# ADC.net
KiCad netlist of a schematic drawn in Altium Designer
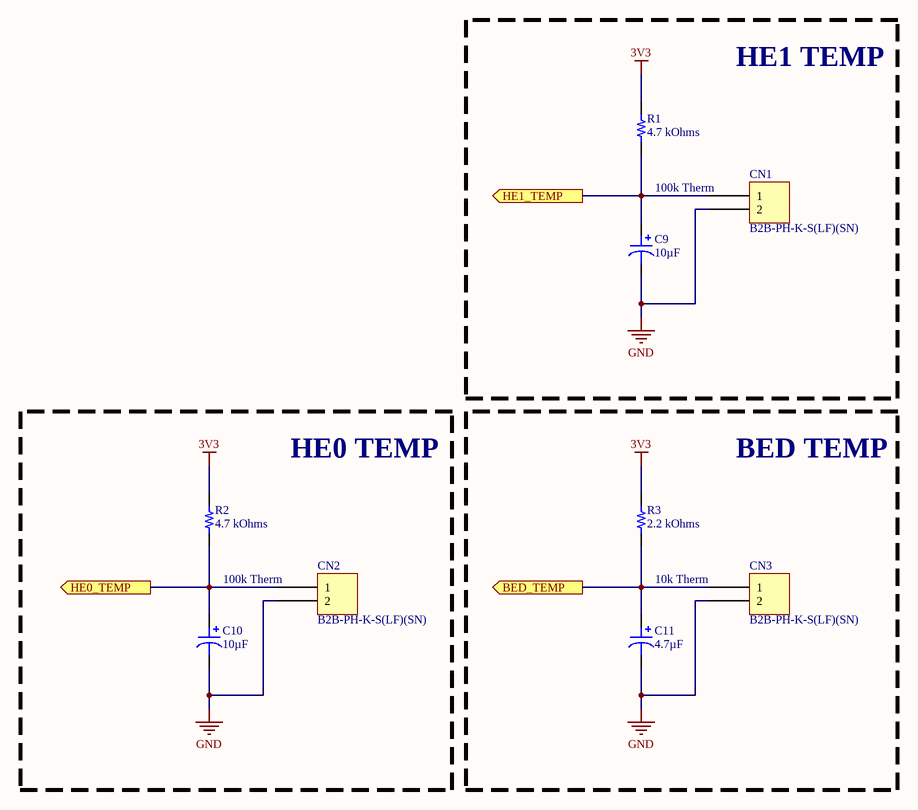
[diagram p0: ADC.SchDoc]

(export (version "E")
  (design (tool "Eeschema 10.0.6"))
  (components
    (comp (ref "C9")
      (value "10µF")
      (footprint "CAP ALSMD 5.3MM H5.4MM")
      (description "CAP ALUM 10UF 20% 16V SMD")
      (fields (field (name "PART NUMBER") "UZP1C100MCL1GB") (field (name "MANUFACTURER") "Nichicon"))
      (libsource (lib "Celestial Altium Library - altium_library") (part "Polarised Capacitor"))
    )
    (comp (ref "C10")
      (value "10µF")
      (footprint "CAP ALSMD 5.3MM H5.4MM")
      (description "CAP ALUM 10UF 20% 16V SMD")
      (fields (field (name "PART NUMBER") "UZP1C100MCL1GB") (field (name "MANUFACTURER") "Nichicon"))
      (libsource (lib "Celestial Altium Library - altium_library") (part "Polarised Capacitor"))
    )
    (comp (ref "C11")
      (value "4.7µF")
      (footprint "CAP ALSMD POLY 4.3MM H5.5MM")
      (description "CAP ALUM POLY 4.7UF 20% 10V SMD")
      (fields (field (name "PART NUMBER") "PCF1A4R7MCL1GB") (field (name "MANUFACTURER") "Nichicon"))
      (libsource (lib "Celestial Altium Library - altium_library") (part "Polarised Capacitor"))
    )
    (comp (ref "CN1")
      (value "B2B-PH-K-S(LF)(SN)")
      (footprint "JST B2B-PH-K")
      (description "CONN HEADER VERT 2POS 2MM")
      (fields (field (name "MANUFACTURER") "JST Sales America Inc."))
      (libsource (lib "Celestial Altium Library - altium_library") (part "2 Pin"))
    )
    (comp (ref "CN2")
      (value "B2B-PH-K-S(LF)(SN)")
      (footprint "JST B2B-PH-K")
      (description "CONN HEADER VERT 2POS 2MM")
      (fields (field (name "MANUFACTURER") "JST Sales America Inc."))
      (libsource (lib "Celestial Altium Library - altium_library") (part "2 Pin"))
    )
    (comp (ref "CN3")
      (value "B2B-PH-K-S(LF)(SN)")
      (footprint "JST B2B-PH-K")
      (description "CONN HEADER VERT 2POS 2MM")
      (fields (field (name "MANUFACTURER") "JST Sales America Inc."))
      (libsource (lib "Celestial Altium Library - altium_library") (part "2 Pin"))
    )
    (comp (ref "R1")
      (value "4.7 kOhms")
      (footprint "RES 0603_1608")
      (description "RES 4.7K OHM 0.1% 1/5W 0603")
      (fields
        (field (name "PART NUMBER") "RS73G1JTTD4701B")
        (field (name "MANUFACTURER") "KOA Speer Electronics, Inc.")
      )
      (libsource (lib "Celestial Altium Library - altium_library") (part "Resistor"))
    )
    (comp (ref "R2")
      (value "4.7 kOhms")
      (footprint "RES 0603_1608")
      (description "RES 4.7K OHM 0.1% 1/5W 0603")
      (fields
        (field (name "PART NUMBER") "RS73G1JTTD4701B")
        (field (name "MANUFACTURER") "KOA Speer Electronics, Inc.")
      )
      (libsource (lib "Celestial Altium Library - altium_library") (part "Resistor"))
    )
    (comp (ref "R3")
      (value "2.2 kOhms")
      (footprint "RES 0603_1608")
      (description "RES 2.2K OHM 0.1% 1/5W 0603")
      (fields
        (field (name "PART NUMBER") "RS73G1JTTD2201B")
        (field (name "MANUFACTURER") "KOA Speer Electronics, Inc.")
      )
      (libsource (lib "Celestial Altium Library - altium_library") (part "Resistor"))
    )
  )
  (nets
    (net (code "1") (name "/BED_TEMP") (class "Default")
      (node (ref "C11") (pin "1") (pinfunction "1_1") (pintype "passive"))
      (node (ref "CN3") (pin "1") (pinfunction "1_1") (pintype "passive"))
      (node (ref "R3") (pin "1") (pinfunction "1_1") (pintype "passive"))
    )
    (net (code "2") (name "/HE0_TEMP") (class "Default")
      (node (ref "C10") (pin "1") (pinfunction "1_1") (pintype "passive"))
      (node (ref "CN2") (pin "1") (pinfunction "1_1") (pintype "passive"))
      (node (ref "R2") (pin "1") (pinfunction "1_1") (pintype "passive"))
    )
    (net (code "3") (name "/HE1_TEMP") (class "Default")
      (node (ref "C9") (pin "1") (pinfunction "1_1") (pintype "passive"))
      (node (ref "CN1") (pin "1") (pinfunction "1_1") (pintype "passive"))
      (node (ref "R1") (pin "1") (pinfunction "1_1") (pintype "passive"))
    )
    (net (code "4") (name "3V3") (class "Default")
      (node (ref "R1") (pin "2") (pinfunction "2_2") (pintype "passive"))
      (node (ref "R2") (pin "2") (pinfunction "2_2") (pintype "passive"))
      (node (ref "R3") (pin "2") (pinfunction "2_2") (pintype "passive"))
    )
    (net (code "5") (name "GND") (class "Default")
      (node (ref "C10") (pin "2") (pinfunction "2_2") (pintype "passive"))
      (node (ref "C11") (pin "2") (pinfunction "2_2") (pintype "passive"))
      (node (ref "C9") (pin "2") (pinfunction "2_2") (pintype "passive"))
      (node (ref "CN1") (pin "2") (pinfunction "2_2") (pintype "passive"))
      (node (ref "CN2") (pin "2") (pinfunction "2_2") (pintype "passive"))
      (node (ref "CN3") (pin "2") (pinfunction "2_2") (pintype "passive"))
    )
  )
)
